# BSK1.net
KiCad netlist of a schematic drawn in EAGLE
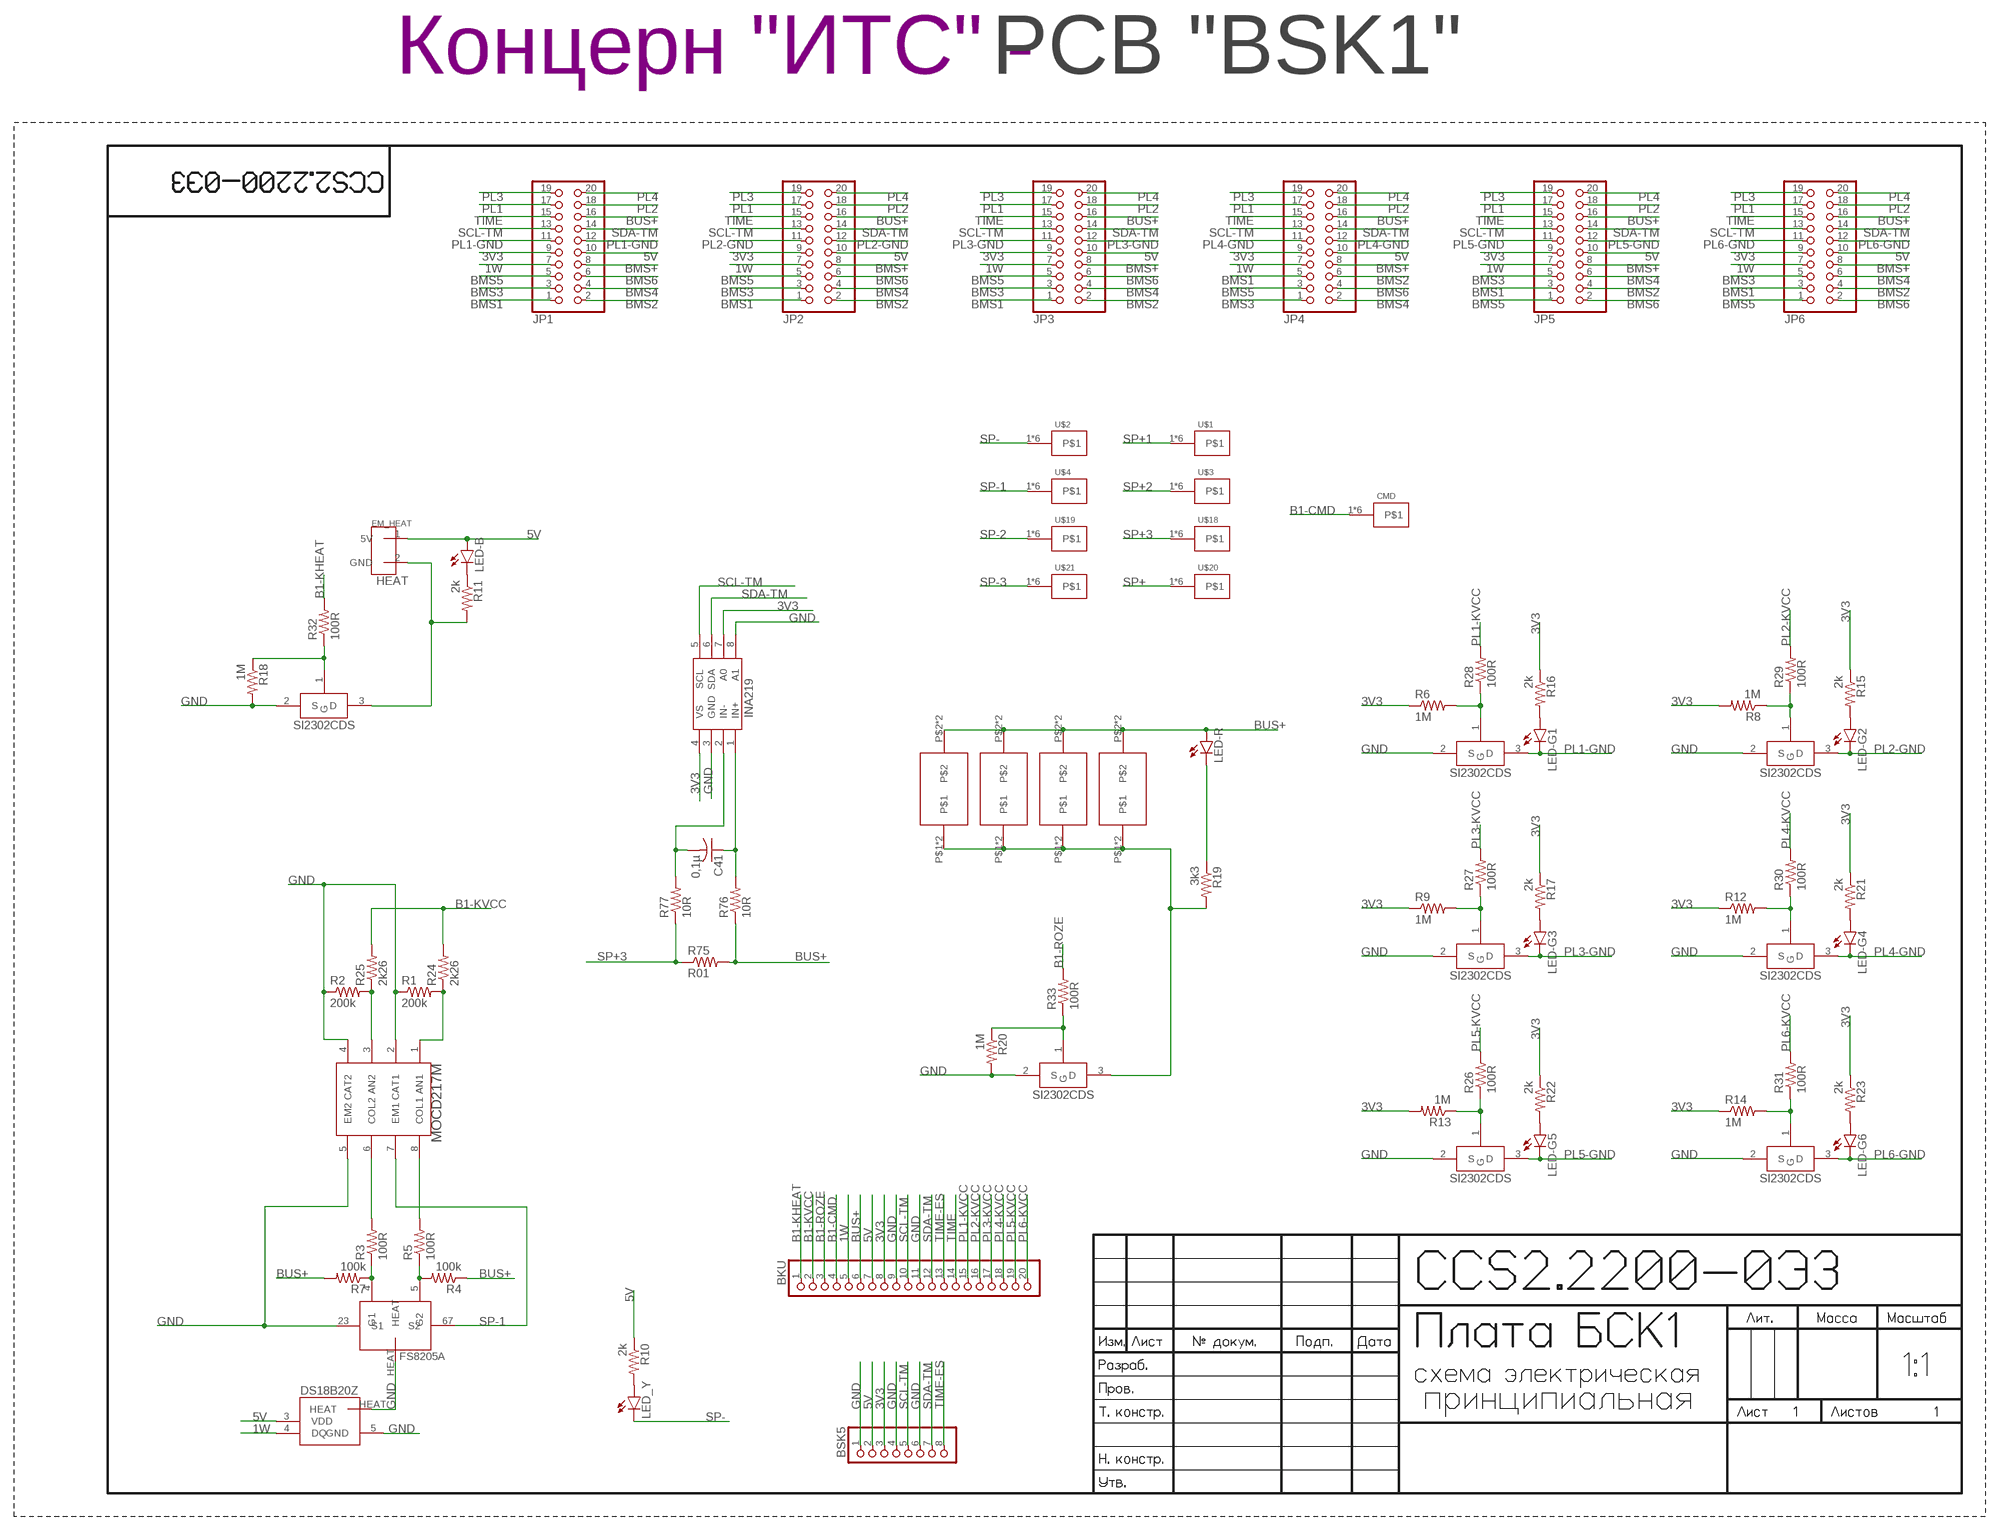
[diagram p0: schematic, sheet 1]

(export (version "E")
  (design (tool "Eeschema 10.0.6"))
  (components
    (comp (ref "BKU")
      (value "PINHD-1X20")
      (footprint "eagle-import:1X20")
      (libsource (lib "eagle-import") (part "PINHD-1X20"))
    )
    (comp (ref "BSK5")
      (value "PINHD-1X8")
      (footprint "eagle-import:1X08")
      (libsource (lib "eagle-import") (part "PINHD-1X8"))
    )
    (comp (ref "C41")
      (value "0,1µ")
      (footprint "eagle-import:C0603")
      (libsource (lib "eagle-import") (part "C-USC0603"))
    )
    (comp (ref "CMD")
      (value "KCONNECTQUAD")
      (footprint "eagle-import:KCONNECT_QUAD")
      (libsource (lib "eagle-import") (part "KCONNECTQUAD"))
    )
    (comp (ref "DS18B20Z")
      (value "DS18B20Z")
      (footprint "eagle-import:SOIC8+HEAT_S")
      (libsource (lib "eagle-import") (part "DS18B20Z"))
    )
    (comp (ref "FS8205")
      (value "FS8205A+")
      (footprint "eagle-import:FS8205A+")
      (libsource (lib "eagle-import") (part "FS8205A+"))
    )
    (comp (ref "INA")
      (value "INA219AID")
      (footprint "eagle-import:SOT23-8")
      (libsource (lib "eagle-import") (part "INA219AID"))
    )
    (comp (ref "JP1")
      (value "PINHD-2X10")
      (footprint "eagle-import:2X10")
      (libsource (lib "eagle-import") (part "PINHD-2X10"))
    )
    (comp (ref "JP2")
      (value "PINHD-2X10")
      (footprint "eagle-import:2X10")
      (libsource (lib "eagle-import") (part "PINHD-2X10"))
    )
    (comp (ref "JP3")
      (value "PINHD-2X10")
      (footprint "eagle-import:2X10")
      (libsource (lib "eagle-import") (part "PINHD-2X10"))
    )
    (comp (ref "JP4")
      (value "PINHD-2X10")
      (footprint "eagle-import:2X10")
      (libsource (lib "eagle-import") (part "PINHD-2X10"))
    )
    (comp (ref "JP5")
      (value "PINHD-2X10")
      (footprint "eagle-import:2X10")
      (libsource (lib "eagle-import") (part "PINHD-2X10"))
    )
    (comp (ref "JP6")
      (value "PINHD-2X10")
      (footprint "eagle-import:2X10")
      (libsource (lib "eagle-import") (part "PINHD-2X10"))
    )
    (comp (ref "LED-B")
      (value "LEDCHIPLED_0603")
      (footprint "eagle-import:CHIPLED_0603")
      (libsource (lib "eagle-import") (part "LEDCHIPLED_0603"))
    )
    (comp (ref "LED-G1")
      (value "LEDCHIPLED_0603")
      (footprint "eagle-import:CHIPLED_0603")
      (libsource (lib "eagle-import") (part "LEDCHIPLED_0603"))
    )
    (comp (ref "LED-G2")
      (value "LEDCHIPLED_0603")
      (footprint "eagle-import:CHIPLED_0603")
      (libsource (lib "eagle-import") (part "LEDCHIPLED_0603"))
    )
    (comp (ref "LED-G3")
      (value "LEDCHIPLED_0603")
      (footprint "eagle-import:CHIPLED_0603")
      (libsource (lib "eagle-import") (part "LEDCHIPLED_0603"))
    )
    (comp (ref "LED-G4")
      (value "LEDCHIPLED_0603")
      (footprint "eagle-import:CHIPLED_0603")
      (libsource (lib "eagle-import") (part "LEDCHIPLED_0603"))
    )
    (comp (ref "LED-G5")
      (value "LEDCHIPLED_0603")
      (footprint "eagle-import:CHIPLED_0603")
      (libsource (lib "eagle-import") (part "LEDCHIPLED_0603"))
    )
    (comp (ref "LED-G6")
      (value "LEDCHIPLED_0603")
      (footprint "eagle-import:CHIPLED_0603")
      (libsource (lib "eagle-import") (part "LEDCHIPLED_0603"))
    )
    (comp (ref "LED-R")
      (value "LEDCHIPLED_0603")
      (footprint "eagle-import:CHIPLED_0603")
      (libsource (lib "eagle-import") (part "LEDCHIPLED_0603"))
    )
    (comp (ref "LED_Y")
      (value "LAP4-BOTTOM")
      (footprint "eagle-import:P47F-BOTTOM")
      (libsource (lib "eagle-import") (part "P4-BOTTOMLA"))
    )
    (comp (ref "R1")
      (value "200k")
      (footprint "eagle-import:R0603")
      (libsource (lib "eagle-import") (part "resistor_R-US_R0603"))
    )
    (comp (ref "R2")
      (value "200k")
      (footprint "eagle-import:R0603")
      (libsource (lib "eagle-import") (part "resistor_R-US_R0603"))
    )
    (comp (ref "R3")
      (value "100R")
      (footprint "eagle-import:R0603")
      (libsource (lib "eagle-import") (part "resistor_R-US_R0603"))
    )
    (comp (ref "R4")
      (value "100k")
      (footprint "eagle-import:R0603")
      (libsource (lib "eagle-import") (part "resistor_R-US_R0603"))
    )
    (comp (ref "R5")
      (value "100R")
      (footprint "eagle-import:R0603")
      (libsource (lib "eagle-import") (part "resistor_R-US_R0603"))
    )
    (comp (ref "R6")
      (value "1M")
      (footprint "eagle-import:R0603")
      (libsource (lib "eagle-import") (part "resistor_R-US_R0603"))
    )
    (comp (ref "R7")
      (value "100k")
      (footprint "eagle-import:R0603")
      (libsource (lib "eagle-import") (part "resistor_R-US_R0603"))
    )
    (comp (ref "R8")
      (value "1M")
      (footprint "eagle-import:R0603")
      (libsource (lib "eagle-import") (part "resistor_R-US_R0603"))
    )
    (comp (ref "R9")
      (value "1M")
      (footprint "eagle-import:R0603")
      (libsource (lib "eagle-import") (part "resistor_R-US_R0603"))
    )
    (comp (ref "R10")
      (value "2k")
      (footprint "eagle-import:R0603")
      (libsource (lib "eagle-import") (part "resistor_R-US_R0603"))
    )
    (comp (ref "R11")
      (value "2k")
      (footprint "eagle-import:R0603")
      (libsource (lib "eagle-import") (part "resistor_R-US_R0603"))
    )
    (comp (ref "R12")
      (value "1M")
      (footprint "eagle-import:R0603")
      (libsource (lib "eagle-import") (part "resistor_R-US_R0603"))
    )
    (comp (ref "R13")
      (value "1M")
      (footprint "eagle-import:R0603")
      (libsource (lib "eagle-import") (part "resistor_R-US_R0603"))
    )
    (comp (ref "R14")
      (value "1M")
      (footprint "eagle-import:R0603")
      (libsource (lib "eagle-import") (part "resistor_R-US_R0603"))
    )
    (comp (ref "R15")
      (value "2k")
      (footprint "eagle-import:R0603")
      (libsource (lib "eagle-import") (part "resistor_R-US_R0603"))
    )
    (comp (ref "R16")
      (value "2k")
      (footprint "eagle-import:R0603")
      (libsource (lib "eagle-import") (part "resistor_R-US_R0603"))
    )
    (comp (ref "R17")
      (value "2k")
      (footprint "eagle-import:R0603")
      (libsource (lib "eagle-import") (part "resistor_R-US_R0603"))
    )
    (comp (ref "R18")
      (value "1M")
      (footprint "eagle-import:R0603")
      (libsource (lib "eagle-import") (part "resistor_R-US_R0603"))
    )
    (comp (ref "R19")
      (value "3k3")
      (footprint "eagle-import:R0603")
      (libsource (lib "eagle-import") (part "resistor_R-US_R0603"))
    )
    (comp (ref "R20")
      (value "1M")
      (footprint "eagle-import:R0603")
      (libsource (lib "eagle-import") (part "resistor_R-US_R0603"))
    )
    (comp (ref "R21")
      (value "2k")
      (footprint "eagle-import:R0603")
      (libsource (lib "eagle-import") (part "resistor_R-US_R0603"))
    )
    (comp (ref "R22")
      (value "2k")
      (footprint "eagle-import:R0603")
      (libsource (lib "eagle-import") (part "resistor_R-US_R0603"))
    )
    (comp (ref "R23")
      (value "2k")
      (footprint "eagle-import:R0603")
      (libsource (lib "eagle-import") (part "resistor_R-US_R0603"))
    )
    (comp (ref "R24")
      (value "2k26")
      (footprint "eagle-import:R0603")
      (libsource (lib "eagle-import") (part "resistor_R-US_R0603"))
    )
    (comp (ref "R25")
      (value "2k26")
      (footprint "eagle-import:R0603")
      (libsource (lib "eagle-import") (part "resistor_R-US_R0603"))
    )
    (comp (ref "R26")
      (value "100R")
      (footprint "eagle-import:R0603")
      (libsource (lib "eagle-import") (part "resistor_R-US_R0603"))
    )
    (comp (ref "R27")
      (value "100R")
      (footprint "eagle-import:R0603")
      (libsource (lib "eagle-import") (part "resistor_R-US_R0603"))
    )
    (comp (ref "R28")
      (value "100R")
      (footprint "eagle-import:R0603")
      (libsource (lib "eagle-import") (part "resistor_R-US_R0603"))
    )
    (comp (ref "R29")
      (value "100R")
      (footprint "eagle-import:R0603")
      (libsource (lib "eagle-import") (part "resistor_R-US_R0603"))
    )
    (comp (ref "R30")
      (value "100R")
      (footprint "eagle-import:R0603")
      (libsource (lib "eagle-import") (part "resistor_R-US_R0603"))
    )
    (comp (ref "R31")
      (value "100R")
      (footprint "eagle-import:R0603")
      (libsource (lib "eagle-import") (part "resistor_R-US_R0603"))
    )
    (comp (ref "R32")
      (value "100R")
      (footprint "eagle-import:R0603")
      (libsource (lib "eagle-import") (part "resistor_R-US_R0603"))
    )
    (comp (ref "R33")
      (value "100R")
      (footprint "eagle-import:R0603")
      (libsource (lib "eagle-import") (part "resistor_R-US_R0603"))
    )
    (comp (ref "R75")
      (value "R01")
      (footprint "eagle-import:R2512")
      (libsource (lib "eagle-import") (part "R-US_R2512"))
    )
    (comp (ref "R76")
      (value "10R")
      (footprint "eagle-import:R0603")
      (libsource (lib "eagle-import") (part "resistor_R-US_R0603"))
    )
    (comp (ref "R77")
      (value "10R")
      (footprint "eagle-import:R0603")
      (libsource (lib "eagle-import") (part "resistor_R-US_R0603"))
    )
    (comp (ref "SI2302-1")
      (value "SI2302CDS")
      (footprint "eagle-import:SOT23-3")
      (libsource (lib "eagle-import") (part "SI2302CDS"))
    )
    (comp (ref "SI2302-2")
      (value "SI2302CDS")
      (footprint "eagle-import:SOT23-3")
      (libsource (lib "eagle-import") (part "SI2302CDS"))
    )
    (comp (ref "SI2302-3")
      (value "SI2302CDS")
      (footprint "eagle-import:SOT23-3")
      (libsource (lib "eagle-import") (part "SI2302CDS"))
    )
    (comp (ref "SI2302-4")
      (value "SI2302CDS")
      (footprint "eagle-import:SOT23-3")
      (libsource (lib "eagle-import") (part "SI2302CDS"))
    )
    (comp (ref "SI2302-5")
      (value "SI2302CDS")
      (footprint "eagle-import:SOT23-3")
      (libsource (lib "eagle-import") (part "SI2302CDS"))
    )
    (comp (ref "SI2302-6")
      (value "SI2302CDS")
      (footprint "eagle-import:SOT23-3")
      (libsource (lib "eagle-import") (part "SI2302CDS"))
    )
    (comp (ref "SI2302-7")
      (value "SI2302CDS")
      (footprint "eagle-import:SOT23-3")
      (libsource (lib "eagle-import") (part "SI2302CDS"))
    )
    (comp (ref "SI2302-8")
      (value "SI2302CDS")
      (footprint "eagle-import:SOT23-3")
      (libsource (lib "eagle-import") (part "SI2302CDS"))
    )
    (comp (ref "U$1")
      (value "KCONNECT")
      (footprint "eagle-import:KCONNECT")
      (libsource (lib "eagle-import") (part "KCONNECT"))
    )
    (comp (ref "U$2")
      (value "KCONNECT")
      (footprint "eagle-import:KCONNECT")
      (libsource (lib "eagle-import") (part "KCONNECT"))
    )
    (comp (ref "U$3")
      (value "KCONNECT")
      (footprint "eagle-import:KCONNECT")
      (libsource (lib "eagle-import") (part "KCONNECT"))
    )
    (comp (ref "U$4")
      (value "KCONNECT")
      (footprint "eagle-import:KCONNECT")
      (libsource (lib "eagle-import") (part "KCONNECT"))
    )
    (comp (ref "U$18")
      (value "KCONNECT")
      (footprint "eagle-import:KCONNECT")
      (libsource (lib "eagle-import") (part "KCONNECT"))
    )
    (comp (ref "U$19")
      (value "KCONNECT")
      (footprint "eagle-import:KCONNECT")
      (libsource (lib "eagle-import") (part "KCONNECT"))
    )
    (comp (ref "U$20")
      (value "KCONNECT")
      (footprint "eagle-import:KCONNECT")
      (libsource (lib "eagle-import") (part "KCONNECT"))
    )
    (comp (ref "U$21")
      (value "KCONNECT")
      (footprint "eagle-import:KCONNECT")
      (libsource (lib "eagle-import") (part "KCONNECT"))
    )
    (comp (ref "U$22")
      (value "MOCD")
      (footprint "eagle-import:SOIC8")
      (libsource (lib "eagle-import") (part "MOCD217M"))
    )
    (comp (ref "U$24")
      (value "EM_HEAT")
      (footprint "eagle-import:EM_HEAT")
      (libsource (lib "eagle-import") (part "EM_HEAT"))
    )
    (comp (ref "U$26")
      (value "PCB \"BSK1\"")
      (footprint "eagle-import:ITS-LOGO")
      (libsource (lib "eagle-import") (part "ITS-LOGOPCB-{dblquote}{dblquote}"))
    )
    (comp (ref "U$27")
      (value "GRAFITGRAFIT4_2")
      (footprint "eagle-import:GRAFIT4_2")
      (libsource (lib "eagle-import") (part "GRAFITGRAFIT4_2"))
    )
    (comp (ref "U$28")
      (value "GRAFITGRAFIT4_2")
      (footprint "eagle-import:GRAFIT4_2")
      (libsource (lib "eagle-import") (part "GRAFITGRAFIT4_2"))
    )
    (comp (ref "U$29")
      (value "GRAFITGRAFIT4_2")
      (footprint "eagle-import:GRAFIT4_2")
      (libsource (lib "eagle-import") (part "GRAFITGRAFIT4_2"))
    )
    (comp (ref "U$30")
      (value "GRAFITGRAFIT4_2")
      (footprint "eagle-import:GRAFIT4_2")
      (libsource (lib "eagle-import") (part "GRAFITGRAFIT4_2"))
    )
  )
  (nets
    (net (code "1") (name "/1W") (class "Default")
      (node (ref "BKU") (pin "5") (pinfunction "5_5") (pintype "passive"))
      (node (ref "DS18B20Z") (pin "4") (pinfunction "DQ_4") (pintype "bidirectional"))
      (node (ref "JP1") (pin "7") (pinfunction "7_7") (pintype "passive"))
      (node (ref "JP2") (pin "7") (pinfunction "7_7") (pintype "passive"))
      (node (ref "JP3") (pin "7") (pinfunction "7_7") (pintype "passive"))
      (node (ref "JP4") (pin "7") (pinfunction "7_7") (pintype "passive"))
      (node (ref "JP5") (pin "7") (pinfunction "7_7") (pintype "passive"))
      (node (ref "JP6") (pin "7") (pinfunction "7_7") (pintype "passive"))
    )
    (net (code "2") (name "/3V3") (class "Default")
      (node (ref "BKU") (pin "8") (pinfunction "8_8") (pintype "passive"))
      (node (ref "BSK5") (pin "3") (pinfunction "3_3") (pintype "passive"))
      (node (ref "INA") (pin "4") (pinfunction "VS_4") (pintype "bidirectional"))
      (node (ref "INA") (pin "7") (pinfunction "A0_7") (pintype "bidirectional"))
      (node (ref "JP1") (pin "9") (pinfunction "9_9") (pintype "passive"))
      (node (ref "JP2") (pin "9") (pinfunction "9_9") (pintype "passive"))
      (node (ref "JP3") (pin "9") (pinfunction "9_9") (pintype "passive"))
      (node (ref "JP4") (pin "9") (pinfunction "9_9") (pintype "passive"))
      (node (ref "JP5") (pin "9") (pinfunction "9_9") (pintype "passive"))
      (node (ref "JP6") (pin "9") (pinfunction "9_9") (pintype "passive"))
      (node (ref "R12") (pin "1") (pinfunction "1_1") (pintype "passive"))
      (node (ref "R13") (pin "2") (pinfunction "2_2") (pintype "passive"))
      (node (ref "R14") (pin "1") (pinfunction "1_1") (pintype "passive"))
      (node (ref "R15") (pin "1") (pinfunction "1_1") (pintype "passive"))
      (node (ref "R16") (pin "1") (pinfunction "1_1") (pintype "passive"))
      (node (ref "R17") (pin "1") (pinfunction "1_1") (pintype "passive"))
      (node (ref "R21") (pin "1") (pinfunction "1_1") (pintype "passive"))
      (node (ref "R22") (pin "1") (pinfunction "1_1") (pintype "passive"))
      (node (ref "R23") (pin "1") (pinfunction "1_1") (pintype "passive"))
      (node (ref "R6") (pin "1") (pinfunction "1_1") (pintype "passive"))
      (node (ref "R8") (pin "2") (pinfunction "2_2") (pintype "passive"))
      (node (ref "R9") (pin "1") (pinfunction "1_1") (pintype "passive"))
    )
    (net (code "3") (name "/5V") (class "Default")
      (node (ref "BKU") (pin "7") (pinfunction "7_7") (pintype "passive"))
      (node (ref "BSK5") (pin "2") (pinfunction "2_2") (pintype "passive"))
      (node (ref "DS18B20Z") (pin "3") (pinfunction "VDD_3") (pintype "bidirectional"))
      (node (ref "JP1") (pin "10") (pinfunction "10_10") (pintype "passive"))
      (node (ref "JP2") (pin "10") (pinfunction "10_10") (pintype "passive"))
      (node (ref "JP3") (pin "10") (pinfunction "10_10") (pintype "passive"))
      (node (ref "JP4") (pin "10") (pinfunction "10_10") (pintype "passive"))
      (node (ref "JP5") (pin "10") (pinfunction "10_10") (pintype "passive"))
      (node (ref "JP6") (pin "10") (pinfunction "10_10") (pintype "passive"))
      (node (ref "LED-B") (pin "A") (pinfunction "A_A") (pintype "passive"))
      (node (ref "R10") (pin "1") (pinfunction "1_1") (pintype "passive"))
      (node (ref "U$24") (pin "1") (pinfunction "5V_1") (pintype "bidirectional"))
    )
    (net (code "4") (name "/B1-CMD") (class "Default")
      (node (ref "BKU") (pin "4") (pinfunction "4_4") (pintype "passive"))
      (node (ref "CMD") (pin "1") (pinfunction "P$1_1") (pintype "bidirectional"))
      (node (ref "CMD") (pin "2") (pinfunction "P$1_2") (pintype "bidirectional"))
      (node (ref "CMD") (pin "3") (pinfunction "P$1_3") (pintype "bidirectional"))
      (node (ref "CMD") (pin "4") (pinfunction "P$1_4") (pintype "bidirectional"))
      (node (ref "CMD") (pin "P$1") (pinfunction "P$1_P$1") (pintype "bidirectional"))
      (node (ref "CMD") (pin "P$2") (pinfunction "P$1_P$2") (pintype "bidirectional"))
    )
    (net (code "5") (name "/B1-KHEAT") (class "Default")
      (node (ref "BKU") (pin "1") (pinfunction "1_1") (pintype "passive"))
      (node (ref "R32") (pin "2") (pinfunction "2_2") (pintype "passive"))
    )
    (net (code "6") (name "/B1-KVCC") (class "Default")
      (node (ref "BKU") (pin "2") (pinfunction "2_2") (pintype "passive"))
      (node (ref "R24") (pin "2") (pinfunction "2_2") (pintype "passive"))
      (node (ref "R25") (pin "2") (pinfunction "2_2") (pintype "passive"))
    )
    (net (code "7") (name "/B1-ROZE") (class "Default")
      (node (ref "BKU") (pin "3") (pinfunction "3_3") (pintype "passive"))
      (node (ref "R33") (pin "2") (pinfunction "2_2") (pintype "passive"))
    )
    (net (code "8") (name "/BMS+") (class "Default")
      (node (ref "JP1") (pin "8") (pinfunction "8_8") (pintype "passive"))
      (node (ref "JP2") (pin "8") (pinfunction "8_8") (pintype "passive"))
      (node (ref "JP3") (pin "8") (pinfunction "8_8") (pintype "passive"))
      (node (ref "JP4") (pin "8") (pinfunction "8_8") (pintype "passive"))
      (node (ref "JP5") (pin "8") (pinfunction "8_8") (pintype "passive"))
      (node (ref "JP6") (pin "8") (pinfunction "8_8") (pintype "passive"))
    )
    (net (code "9") (name "/BMS1") (class "Default")
      (node (ref "JP1") (pin "1") (pinfunction "1_1") (pintype "passive"))
      (node (ref "JP2") (pin "1") (pinfunction "1_1") (pintype "passive"))
      (node (ref "JP3") (pin "1") (pinfunction "1_1") (pintype "passive"))
      (node (ref "JP4") (pin "5") (pinfunction "5_5") (pintype "passive"))
      (node (ref "JP5") (pin "3") (pinfunction "3_3") (pintype "passive"))
      (node (ref "JP6") (pin "3") (pinfunction "3_3") (pintype "passive"))
    )
    (net (code "10") (name "/BMS2") (class "Default")
      (node (ref "JP1") (pin "2") (pinfunction "2_2") (pintype "passive"))
      (node (ref "JP2") (pin "2") (pinfunction "2_2") (pintype "passive"))
      (node (ref "JP3") (pin "2") (pinfunction "2_2") (pintype "passive"))
      (node (ref "JP4") (pin "6") (pinfunction "6_6") (pintype "passive"))
      (node (ref "JP5") (pin "4") (pinfunction "4_4") (pintype "passive"))
      (node (ref "JP6") (pin "4") (pinfunction "4_4") (pintype "passive"))
    )
    (net (code "11") (name "/BMS3") (class "Default")
      (node (ref "JP1") (pin "3") (pinfunction "3_3") (pintype "passive"))
      (node (ref "JP2") (pin "3") (pinfunction "3_3") (pintype "passive"))
      (node (ref "JP3") (pin "3") (pinfunction "3_3") (pintype "passive"))
      (node (ref "JP4") (pin "1") (pinfunction "1_1") (pintype "passive"))
      (node (ref "JP5") (pin "5") (pinfunction "5_5") (pintype "passive"))
      (node (ref "JP6") (pin "5") (pinfunction "5_5") (pintype "passive"))
    )
    (net (code "12") (name "/BMS4") (class "Default")
      (node (ref "JP1") (pin "4") (pinfunction "4_4") (pintype "passive"))
      (node (ref "JP2") (pin "4") (pinfunction "4_4") (pintype "passive"))
      (node (ref "JP3") (pin "4") (pinfunction "4_4") (pintype "passive"))
      (node (ref "JP4") (pin "2") (pinfunction "2_2") (pintype "passive"))
      (node (ref "JP5") (pin "6") (pinfunction "6_6") (pintype "passive"))
      (node (ref "JP6") (pin "6") (pinfunction "6_6") (pintype "passive"))
    )
    (net (code "13") (name "/BMS5") (class "Default")
      (node (ref "JP1") (pin "5") (pinfunction "5_5") (pintype "passive"))
      (node (ref "JP2") (pin "5") (pinfunction "5_5") (pintype "passive"))
      (node (ref "JP3") (pin "5") (pinfunction "5_5") (pintype "passive"))
      (node (ref "JP4") (pin "3") (pinfunction "3_3") (pintype "passive"))
      (node (ref "JP5") (pin "1") (pinfunction "1_1") (pintype "passive"))
      (node (ref "JP6") (pin "1") (pinfunction "1_1") (pintype "passive"))
    )
    (net (code "14") (name "/BMS6") (class "Default")
      (node (ref "JP1") (pin "6") (pinfunction "6_6") (pintype "passive"))
      (node (ref "JP2") (pin "6") (pinfunction "6_6") (pintype "passive"))
      (node (ref "JP3") (pin "6") (pinfunction "6_6") (pintype "passive"))
      (node (ref "JP4") (pin "4") (pinfunction "4_4") (pintype "passive"))
      (node (ref "JP5") (pin "2") (pinfunction "2_2") (pintype "passive"))
      (node (ref "JP6") (pin "2") (pinfunction "2_2") (pintype "passive"))
    )
    (net (code "15") (name "/BUS+") (class "Default")
      (node (ref "BKU") (pin "6") (pinfunction "6_6") (pintype "passive"))
      (node (ref "JP1") (pin "16") (pinfunction "16_16") (pintype "passive"))
      (node (ref "JP2") (pin "16") (pinfunction "16_16") (pintype "passive"))
      (node (ref "JP3") (pin "16") (pinfunction "16_16") (pintype "passive"))
      (node (ref "JP4") (pin "16") (pinfunction "16_16") (pintype "passive"))
      (node (ref "JP5") (pin "16") (pinfunction "16_16") (pintype "passive"))
      (node (ref "JP6") (pin "16") (pinfunction "16_16") (pintype "passive"))
      (node (ref "LED-R") (pin "A") (pinfunction "A_A") (pintype "passive"))
      (node (ref "R4") (pin "1") (pinfunction "1_1") (pintype "passive"))
      (node (ref "R7") (pin "2") (pinfunction "2_2") (pintype "passive"))
      (node (ref "R75") (pin "2") (pinfunction "2_2") (pintype "passive"))
      (node (ref "R76") (pin "1") (pinfunction "1_1") (pintype "passive"))
      (node (ref "U$27") (pin "P$2") (pinfunction "P$2_P$2") (pintype "bidirectional"))
      (node (ref "U$27") (pin "P$5") (pinfunction "P$2_P$5") (pintype "bidirectional"))
      (node (ref "U$28") (pin "P$2") (pinfunction "P$2_P$2") (pintype "bidirectional"))
      (node (ref "U$28") (pin "P$5") (pinfunction "P$2_P$5") (pintype "bidirectional"))
      (node (ref "U$29") (pin "P$2") (pinfunction "P$2_P$2") (pintype "bidirectional"))
      (node (ref "U$29") (pin "P$5") (pinfunction "P$2_P$5") (pintype "bidirectional"))
      (node (ref "U$30") (pin "P$2") (pinfunction "P$2_P$2") (pintype "bidirectional"))
      (node (ref "U$30") (pin "P$5") (pinfunction "P$2_P$5") (pintype "bidirectional"))
    )
    (net (code "16") (name "/GND") (class "Default")
      (node (ref "BKU") (pin "11") (pinfunction "11_11") (pintype "passive"))
      (node (ref "BKU") (pin "9") (pinfunction "9_9") (pintype "passive"))
      (node (ref "BSK5") (pin "1") (pinfunction "1_1") (pintype "passive"))
      (node (ref "BSK5") (pin "4") (pinfunction "4_4") (pintype "passive"))
      (node (ref "BSK5") (pin "6") (pinfunction "6_6") (pintype "passive"))
      (node (ref "DS18B20Z") (pin "5") (pinfunction "GND_5") (pintype "bidirectional"))
      (node (ref "DS18B20Z") (pin "HEAT") (pinfunction "HEAT_HEAT") (pintype "bidirectional"))
      (node (ref "FS8205") (pin "23") (pinfunction "S1_23") (pintype "bidirectional"))
      (node (ref "FS8205") (pin "HEAT") (pinfunction "HEAT_HEAT") (pintype "bidirectional"))
      (node (ref "INA") (pin "3") (pinfunction "GND_3") (pintype "bidirectional"))
      (node (ref "INA") (pin "8") (pinfunction "A1_8") (pintype "bidirectional"))
      (node (ref "R1") (pin "1") (pinfunction "1_1") (pintype "passive"))
      (node (ref "R18") (pin "2") (pinfunction "2_2") (pintype "passive"))
      (node (ref "R2") (pin "1") (pinfunction "1_1") (pintype "passive"))
      (node (ref "R20") (pin "2") (pinfunction "2_2") (pintype "passive"))
      (node (ref "SI2302-1") (pin "2") (pinfunction "S_2") (pintype "bidirectional"))
      (node (ref "SI2302-2") (pin "2") (pinfunction "S_2") (pintype "bidirectional"))
      (node (ref "SI2302-3") (pin "2") (pinfunction "S_2") (pintype "bidirectional"))
      (node (ref "SI2302-4") (pin "2") (pinfunction "S_2") (pintype "bidirectional"))
      (node (ref "SI2302-5") (pin "2") (pinfunction "S_2") (pintype "bidirectional"))
      (node (ref "SI2302-6") (pin "2") (pinfunction "S_2") (pintype "bidirectional"))
      (node (ref "SI2302-7") (pin "2") (pinfunction "S_2") (pintype "bidirectional"))
      (node (ref "SI2302-8") (pin "2") (pinfunction "S_2") (pintype "bidirectional"))
      (node (ref "U$22") (pin "2") (pinfunction "CAT1_2") (pintype "bidirectional"))
      (node (ref "U$22") (pin "4") (pinfunction "CAT2_4") (pintype "bidirectional"))
      (node (ref "U$22") (pin "5") (pinfunction "EM2_5") (pintype "bidirectional"))
    )
    (net (code "17") (name "/PL1") (class "Default")
      (node (ref "JP1") (pin "17") (pinfunction "17_17") (pintype "passive"))
      (node (ref "JP2") (pin "17") (pinfunction "17_17") (pintype "passive"))
      (node (ref "JP3") (pin "17") (pinfunction "17_17") (pintype "passive"))
      (node (ref "JP4") (pin "17") (pinfunction "17_17") (pintype "passive"))
      (node (ref "JP5") (pin "17") (pinfunction "17_17") (pintype "passive"))
      (node (ref "JP6") (pin "17") (pinfunction "17_17") (pintype "passive"))
    )
    (net (code "18") (name "/PL1-GND") (class "Default")
      (node (ref "JP1") (pin "11") (pinfunction "11_11") (pintype "passive"))
      (node (ref "JP1") (pin "12") (pinfunction "12_12") (pintype "passive"))
      (node (ref "LED-G1") (pin "C") (pinfunction "C_C") (pintype "passive"))
      (node (ref "SI2302-8") (pin "3") (pinfunction "D_3") (pintype "bidirectional"))
    )
    (net (code "19") (name "/PL1-KVCC") (class "Default")
      (node (ref "BKU") (pin "15") (pinfunction "15_15") (pintype "passive"))
      (node (ref "R28") (pin "2") (pinfunction "2_2") (pintype "passive"))
    )
    (net (code "20") (name "/PL2") (class "Default")
      (node (ref "JP1") (pin "18") (pinfunction "18_18") (pintype "passive"))
      (node (ref "JP2") (pin "18") (pinfunction "18_18") (pintype "passive"))
      (node (ref "JP3") (pin "18") (pinfunction "18_18") (pintype "passive"))
      (node (ref "JP4") (pin "18") (pinfunction "18_18") (pintype "passive"))
      (node (ref "JP5") (pin "18") (pinfunction "18_18") (pintype "passive"))
      (node (ref "JP6") (pin "18") (pinfunction "18_18") (pintype "passive"))
    )
    (net (code "21") (name "/PL2-GND") (class "Default")
      (node (ref "JP2") (pin "11") (pinfunction "11_11") (pintype "passive"))
      (node (ref "JP2") (pin "12") (pinfunction "12_12") (pintype "passive"))
      (node (ref "LED-G2") (pin "C") (pinfunction "C_C") (pintype "passive"))
      (node (ref "SI2302-7") (pin "3") (pinfunction "D_3") (pintype "bidirectional"))
    )
    (net (code "22") (name "/PL2-KVCC") (class "Default")
      (node (ref "BKU") (pin "16") (pinfunction "16_16") (pintype "passive"))
      (node (ref "R29") (pin "2") (pinfunction "2_2") (pintype "passive"))
    )
    (net (code "23") (name "/PL3") (class "Default")
      (node (ref "JP1") (pin "19") (pinfunction "19_19") (pintype "passive"))
      (node (ref "JP2") (pin "19") (pinfunction "19_19") (pintype "passive"))
      (node (ref "JP3") (pin "19") (pinfunction "19_19") (pintype "passive"))
      (node (ref "JP4") (pin "19") (pinfunction "19_19") (pintype "passive"))
      (node (ref "JP5") (pin "19") (pinfunction "19_19") (pintype "passive"))
      (node (ref "JP6") (pin "19") (pinfunction "19_19") (pintype "passive"))
    )
    (net (code "24") (name "/PL3-GND") (class "Default")
      (node (ref "JP3") (pin "11") (pinfunction "11_11") (pintype "passive"))
      (node (ref "JP3") (pin "12") (pinfunction "12_12") (pintype "passive"))
      (node (ref "LED-G3") (pin "C") (pinfunction "C_C") (pintype "passive"))
      (node (ref "SI2302-6") (pin "3") (pinfunction "D_3") (pintype "bidirectional"))
    )
    (net (code "25") (name "/PL3-KVCC") (class "Default")
      (node (ref "BKU") (pin "17") (pinfunction "17_17") (pintype "passive"))
      (node (ref "R27") (pin "2") (pinfunction "2_2") (pintype "passive"))
    )
    (net (code "26") (name "/PL4") (class "Default")
      (node (ref "JP1") (pin "20") (pinfunction "20_20") (pintype "passive"))
      (node (ref "JP2") (pin "20") (pinfunction "20_20") (pintype "passive"))
      (node (ref "JP3") (pin "20") (pinfunction "20_20") (pintype "passive"))
      (node (ref "JP4") (pin "20") (pinfunction "20_20") (pintype "passive"))
      (node (ref "JP5") (pin "20") (pinfunction "20_20") (pintype "passive"))
      (node (ref "JP6") (pin "20") (pinfunction "20_20") (pintype "passive"))
    )
    (net (code "27") (name "/PL4-GND") (class "Default")
      (node (ref "JP4") (pin "11") (pinfunction "11_11") (pintype "passive"))
      (node (ref "JP4") (pin "12") (pinfunction "12_12") (pintype "passive"))
      (node (ref "LED-G4") (pin "C") (pinfunction "C_C") (pintype "passive"))
      (node (ref "SI2302-5") (pin "3") (pinfunction "D_3") (pintype "bidirectional"))
    )
    (net (code "28") (name "/PL4-KVCC") (class "Default")
      (node (ref "BKU") (pin "18") (pinfunction "18_18") (pintype "passive"))
      (node (ref "R30") (pin "2") (pinfunction "2_2") (pintype "passive"))
    )
    (net (code "29") (name "/PL5-GND") (class "Default")
      (node (ref "JP5") (pin "11") (pinfunction "11_11") (pintype "passive"))
      (node (ref "JP5") (pin "12") (pinfunction "12_12") (pintype "passive"))
      (node (ref "LED-G5") (pin "C") (pinfunction "C_C") (pintype "passive"))
      (node (ref "SI2302-4") (pin "3") (pinfunction "D_3") (pintype "bidirectional"))
    )
    (net (code "30") (name "/PL5-KVCC") (class "Default")
      (node (ref "BKU") (pin "19") (pinfunction "19_19") (pintype "passive"))
      (node (ref "R26") (pin "2") (pinfunction "2_2") (pintype "passive"))
    )
    (net (code "31") (name "/PL6-GND") (class "Default")
      (node (ref "JP6") (pin "11") (pinfunction "11_11") (pintype "passive"))
      (node (ref "JP6") (pin "12") (pinfunction "12_12") (pintype "passive"))
      (node (ref "LED-G6") (pin "C") (pinfunction "C_C") (pintype "passive"))
      (node (ref "SI2302-3") (pin "3") (pinfunction "D_3") (pintype "bidirectional"))
    )
    (net (code "32") (name "/PL6-KVCC") (class "Default")
      (node (ref "BKU") (pin "20") (pinfunction "20_20") (pintype "passive"))
      (node (ref "R31") (pin "2") (pinfunction "2_2") (pintype "passive"))
    )
    (net (code "33") (name "/SCL-TM") (class "Default")
      (node (ref "BKU") (pin "10") (pinfunction "10_10") (pintype "passive"))
      (node (ref "BSK5") (pin "5") (pinfunction "5_5") (pintype "passive"))
      (node (ref "INA") (pin "5") (pinfunction "SCL_5") (pintype "bidirectional"))
      (node (ref "JP1") (pin "13") (pinfunction "13_13") (pintype "passive"))
      (node (ref "JP2") (pin "13") (pinfunction "13_13") (pintype "passive"))
      (node (ref "JP3") (pin "13") (pinfunction "13_13") (pintype "passive"))
      (node (ref "JP4") (pin "13") (pinfunction "13_13") (pintype "passive"))
      (node (ref "JP5") (pin "13") (pinfunction "13_13") (pintype "passive"))
      (node (ref "JP6") (pin "13") (pinfunction "13_13") (pintype "passive"))
    )
    (net (code "34") (name "/SDA-TM") (class "Default")
      (node (ref "BKU") (pin "12") (pinfunction "12_12") (pintype "passive"))
      (node (ref "BSK5") (pin "7") (pinfunction "7_7") (pintype "passive"))
      (node (ref "INA") (pin "6") (pinfunction "SDA_6") (pintype "bidirectional"))
      (node (ref "JP1") (pin "14") (pinfunction "14_14") (pintype "passive"))
      (node (ref "JP2") (pin "14") (pinfunction "14_14") (pintype "passive"))
      (node (ref "JP3") (pin "14") (pinfunction "14_14") (pintype "passive"))
      (node (ref "JP4") (pin "14") (pinfunction "14_14") (pintype "passive"))
      (node (ref "JP5") (pin "14") (pinfunction "14_14") (pintype "passive"))
      (node (ref "JP6") (pin "14") (pinfunction "14_14") (pintype "passive"))
    )
    (net (code "35") (name "/SP+") (class "Default")
      (node (ref "U$20") (pin "1") (pinfunction "P$1_1") (pintype "bidirectional"))
      (node (ref "U$20") (pin "2") (pinfunction "P$1_2") (pintype "bidirectional"))
      (node (ref "U$20") (pin "3") (pinfunction "P$1_3") (pintype "bidirectional"))
      (node (ref "U$20") (pin "4") (pinfunction "P$1_4") (pintype "bidirectional"))
      (node (ref "U$20") (pin "P$1") (pinfunction "P$1_P$1") (pintype "bidirectional"))
      (node (ref "U$20") (pin "P$2") (pinfunction "P$1_P$2") (pintype "bidirectional"))
    )
    (net (code "36") (name "/SP+1") (class "Default")
      (node (ref "U$1") (pin "1") (pinfunction "P$1_1") (pintype "bidirectional"))
      (node (ref "U$1") (pin "2") (pinfunction "P$1_2") (pintype "bidirectional"))
      (node (ref "U$1") (pin "3") (pinfunction "P$1_3") (pintype "bidirectional"))
      (node (ref "U$1") (pin "4") (pinfunction "P$1_4") (pintype "bidirectional"))
      (node (ref "U$1") (pin "P$1") (pinfunction "P$1_P$1") (pintype "bidirectional"))
      (node (ref "U$1") (pin "P$2") (pinfunction "P$1_P$2") (pintype "bidirectional"))
    )
    (net (code "37") (name "/SP+2") (class "Default")
      (node (ref "U$3") (pin "1") (pinfunction "P$1_1") (pintype "bidirectional"))
      (node (ref "U$3") (pin "2") (pinfunction "P$1_2") (pintype "bidirectional"))
      (node (ref "U$3") (pin "3") (pinfunction "P$1_3") (pintype "bidirectional"))
      (node (ref "U$3") (pin "4") (pinfunction "P$1_4") (pintype "bidirectional"))
      (node (ref "U$3") (pin "P$1") (pinfunction "P$1_P$1") (pintype "bidirectional"))
      (node (ref "U$3") (pin "P$2") (pinfunction "P$1_P$2") (pintype "bidirectional"))
    )
    (net (code "38") (name "/SP+3") (class "Default")
      (node (ref "R75") (pin "1") (pinfunction "1_1") (pintype "passive"))
      (node (ref "R77") (pin "1") (pinfunction "1_1") (pintype "passive"))
      (node (ref "U$18") (pin "1") (pinfunction "P$1_1") (pintype "bidirectional"))
      (node (ref "U$18") (pin "2") (pinfunction "P$1_2") (pintype "bidirectional"))
      (node (ref "U$18") (pin "3") (pinfunction "P$1_3") (pintype "bidirectional"))
      (node (ref "U$18") (pin "4") (pinfunction "P$1_4") (pintype "bidirectional"))
      (node (ref "U$18") (pin "P$1") (pinfunction "P$1_P$1") (pintype "bidirectional"))
      (node (ref "U$18") (pin "P$2") (pinfunction "P$1_P$2") (pintype "bidirectional"))
    )
    (net (code "39") (name "/SP-") (class "Default")
      (node (ref "LED_Y") (pin "C") (pinfunction "C_C") (pintype "passive"))
      (node (ref "U$2") (pin "1") (pinfunction "P$1_1") (pintype "bidirectional"))
      (node (ref "U$2") (pin "2") (pinfunction "P$1_2") (pintype "bidirectional"))
      (node (ref "U$2") (pin "3") (pinfunction "P$1_3") (pintype "bidirectional"))
      (node (ref "U$2") (pin "4") (pinfunction "P$1_4") (pintype "bidirectional"))
      (node (ref "U$2") (pin "P$1") (pinfunction "P$1_P$1") (pintype "bidirectional"))
      (node (ref "U$2") (pin "P$2") (pinfunction "P$1_P$2") (pintype "bidirectional"))
    )
    (net (code "40") (name "/SP-1") (class "Default")
      (node (ref "FS8205") (pin "67") (pinfunction "S2_67") (pintype "bidirectional"))
      (node (ref "U$22") (pin "7") (pinfunction "EM1_7") (pintype "bidirectional"))
      (node (ref "U$4") (pin "1") (pinfunction "P$1_1") (pintype "bidirectional"))
      (node (ref "U$4") (pin "2") (pinfunction "P$1_2") (pintype "bidirectional"))
      (node (ref "U$4") (pin "3") (pinfunction "P$1_3") (pintype "bidirectional"))
      (node (ref "U$4") (pin "4") (pinfunction "P$1_4") (pintype "bidirectional"))
      (node (ref "U$4") (pin "P$1") (pinfunction "P$1_P$1") (pintype "bidirectional"))
      (node (ref "U$4") (pin "P$2") (pinfunction "P$1_P$2") (pintype "bidirectional"))
    )
    (net (code "41") (name "/SP-2") (class "Default")
      (node (ref "U$19") (pin "1") (pinfunction "P$1_1") (pintype "bidirectional"))
      (node (ref "U$19") (pin "2") (pinfunction "P$1_2") (pintype "bidirectional"))
      (node (ref "U$19") (pin "3") (pinfunction "P$1_3") (pintype "bidirectional"))
      (node (ref "U$19") (pin "4") (pinfunction "P$1_4") (pintype "bidirectional"))
      (node (ref "U$19") (pin "P$1") (pinfunction "P$1_P$1") (pintype "bidirectional"))
      (node (ref "U$19") (pin "P$2") (pinfunction "P$1_P$2") (pintype "bidirectional"))
    )
    (net (code "42") (name "/SP-3") (class "Default")
      (node (ref "U$21") (pin "1") (pinfunction "P$1_1") (pintype "bidirectional"))
      (node (ref "U$21") (pin "2") (pinfunction "P$1_2") (pintype "bidirectional"))
      (node (ref "U$21") (pin "3") (pinfunction "P$1_3") (pintype "bidirectional"))
      (node (ref "U$21") (pin "4") (pinfunction "P$1_4") (pintype "bidirectional"))
      (node (ref "U$21") (pin "P$1") (pinfunction "P$1_P$1") (pintype "bidirectional"))
      (node (ref "U$21") (pin "P$2") (pinfunction "P$1_P$2") (pintype "bidirectional"))
    )
    (net (code "43") (name "/TIME") (class "Default")
      (node (ref "BKU") (pin "14") (pinfunction "14_14") (pintype "passive"))
      (node (ref "JP1") (pin "15") (pinfunction "15_15") (pintype "passive"))
      (node (ref "JP2") (pin "15") (pinfunction "15_15") (pintype "passive"))
      (node (ref "JP3") (pin "15") (pinfunction "15_15") (pintype "passive"))
      (node (ref "JP4") (pin "15") (pinfunction "15_15") (pintype "passive"))
      (node (ref "JP5") (pin "15") (pinfunction "15_15") (pintype "passive"))
      (node (ref "JP6") (pin "15") (pinfunction "15_15") (pintype "passive"))
    )
    (net (code "44") (name "/TIME-ES") (class "Default")
      (node (ref "BKU") (pin "13") (pinfunction "13_13") (pintype "passive"))
      (node (ref "BSK5") (pin "8") (pinfunction "8_8") (pintype "passive"))
    )
    (net (code "45") (name "Net-(FS8205-G1)") (class "Default")
      (node (ref "FS8205") (pin "4") (pinfunction "G1_4") (pintype "bidirectional"))
      (node (ref "R3") (pin "1") (pinfunction "1_1") (pintype "passive"))
      (node (ref "R7") (pin "1") (pinfunction "1_1") (pintype "passive"))
    )
    (net (code "46") (name "Net-(FS8205-G2)") (class "Default")
      (node (ref "FS8205") (pin "5") (pinfunction "G2_5") (pintype "bidirectional"))
      (node (ref "R4") (pin "2") (pinfunction "2_2") (pintype "passive"))
      (node (ref "R5") (pin "1") (pinfunction "1_1") (pintype "passive"))
    )
    (net (code "47") (name "Net-(INA-IN+)") (class "Default")
      (node (ref "C41") (pin "1") (pinfunction "1_1") (pintype "passive"))
      (node (ref "INA") (pin "1") (pinfunction "IN+_1") (pintype "bidirectional"))
      (node (ref "R76") (pin "2") (pinfunction "2_2") (pintype "passive"))
    )
    (net (code "48") (name "Net-(INA-IN-)") (class "Default")
      (node (ref "C41") (pin "2") (pinfunction "2_2") (pintype "passive"))
      (node (ref "INA") (pin "2") (pinfunction "IN-_2") (pintype "bidirectional"))
      (node (ref "R77") (pin "2") (pinfunction "2_2") (pintype "passive"))
    )
    (net (code "49") (name "Net-(LED-B-PadC)") (class "Default")
      (node (ref "LED-B") (pin "C") (pinfunction "C_C") (pintype "passive"))
      (node (ref "R11") (pin "1") (pinfunction "1_1") (pintype "passive"))
    )
    (net (code "50") (name "Net-(LED-G1-PadA)") (class "Default")
      (node (ref "LED-G1") (pin "A") (pinfunction "A_A") (pintype "passive"))
      (node (ref "R16") (pin "2") (pinfunction "2_2") (pintype "passive"))
    )
    (net (code "51") (name "Net-(LED-G2-PadA)") (class "Default")
      (node (ref "LED-G2") (pin "A") (pinfunction "A_A") (pintype "passive"))
      (node (ref "R15") (pin "2") (pinfunction "2_2") (pintype "passive"))
    )
    (net (code "52") (name "Net-(LED-G3-PadA)") (class "Default")
      (node (ref "LED-G3") (pin "A") (pinfunction "A_A") (pintype "passive"))
      (node (ref "R17") (pin "2") (pinfunction "2_2") (pintype "passive"))
    )
    (net (code "53") (name "Net-(LED-G4-PadA)") (class "Default")
      (node (ref "LED-G4") (pin "A") (pinfunction "A_A") (pintype "passive"))
      (node (ref "R21") (pin "2") (pinfunction "2_2") (pintype "passive"))
    )
    (net (code "54") (name "Net-(LED-G5-PadA)") (class "Default")
      (node (ref "LED-G5") (pin "A") (pinfunction "A_A") (pintype "passive"))
      (node (ref "R22") (pin "2") (pinfunction "2_2") (pintype "passive"))
    )
    (net (code "55") (name "Net-(LED-G6-PadA)") (class "Default")
      (node (ref "LED-G6") (pin "A") (pinfunction "A_A") (pintype "passive"))
      (node (ref "R23") (pin "2") (pinfunction "2_2") (pintype "passive"))
    )
    (net (code "56") (name "Net-(LED-R-PadC)") (class "Default")
      (node (ref "LED-R") (pin "C") (pinfunction "C_C") (pintype "passive"))
      (node (ref "R19") (pin "1") (pinfunction "1_1") (pintype "passive"))
    )
    (net (code "57") (name "Net-(LED_Y-PadA)") (class "Default")
      (node (ref "LED_Y") (pin "A") (pinfunction "A_A") (pintype "passive"))
      (node (ref "R10") (pin "2") (pinfunction "2_2") (pintype "passive"))
    )
    (net (code "58") (name "Net-(SI2302-1-D)") (class "Default")
      (node (ref "R11") (pin "2") (pinfunction "2_2") (pintype "passive"))
      (node (ref "SI2302-1") (pin "3") (pinfunction "D_3") (pintype "bidirectional"))
      (node (ref "U$24") (pin "2") (pinfunction "GND_2") (pintype "bidirectional"))
    )
    (net (code "59") (name "Net-(SI2302-1-G)") (class "Default")
      (node (ref "R18") (pin "1") (pinfunction "1_1") (pintype "passive"))
      (node (ref "R32") (pin "1") (pinfunction "1_1") (pintype "passive"))
      (node (ref "SI2302-1") (pin "1") (pinfunction "G_1") (pintype "bidirectional"))
    )
    (net (code "60") (name "Net-(SI2302-2-D)") (class "Default")
      (node (ref "R19") (pin "2") (pinfunction "2_2") (pintype "passive"))
      (node (ref "SI2302-2") (pin "3") (pinfunction "D_3") (pintype "bidirectional"))
      (node (ref "U$27") (pin "P$1") (pinfunction "P$1_P$1") (pintype "bidirectional"))
      (node (ref "U$27") (pin "P$4") (pinfunction "P$1_P$4") (pintype "bidirectional"))
      (node (ref "U$28") (pin "P$1") (pinfunction "P$1_P$1") (pintype "bidirectional"))
      (node (ref "U$28") (pin "P$4") (pinfunction "P$1_P$4") (pintype "bidirectional"))
      (node (ref "U$29") (pin "P$1") (pinfunction "P$1_P$1") (pintype "bidirectional"))
      (node (ref "U$29") (pin "P$4") (pinfunction "P$1_P$4") (pintype "bidirectional"))
      (node (ref "U$30") (pin "P$1") (pinfunction "P$1_P$1") (pintype "bidirectional"))
      (node (ref "U$30") (pin "P$4") (pinfunction "P$1_P$4") (pintype "bidirectional"))
    )
    (net (code "61") (name "Net-(SI2302-2-G)") (class "Default")
      (node (ref "R20") (pin "1") (pinfunction "1_1") (pintype "passive"))
      (node (ref "R33") (pin "1") (pinfunction "1_1") (pintype "passive"))
      (node (ref "SI2302-2") (pin "1") (pinfunction "G_1") (pintype "bidirectional"))
    )
    (net (code "62") (name "Net-(SI2302-3-G)") (class "Default")
      (node (ref "R14") (pin "2") (pinfunction "2_2") (pintype "passive"))
      (node (ref "R31") (pin "1") (pinfunction "1_1") (pintype "passive"))
      (node (ref "SI2302-3") (pin "1") (pinfunction "G_1") (pintype "bidirectional"))
    )
    (net (code "63") (name "Net-(SI2302-4-G)") (class "Default")
      (node (ref "R13") (pin "1") (pinfunction "1_1") (pintype "passive"))
      (node (ref "R26") (pin "1") (pinfunction "1_1") (pintype "passive"))
      (node (ref "SI2302-4") (pin "1") (pinfunction "G_1") (pintype "bidirectional"))
    )
    (net (code "64") (name "Net-(SI2302-5-G)") (class "Default")
      (node (ref "R12") (pin "2") (pinfunction "2_2") (pintype "passive"))
      (node (ref "R30") (pin "1") (pinfunction "1_1") (pintype "passive"))
      (node (ref "SI2302-5") (pin "1") (pinfunction "G_1") (pintype "bidirectional"))
    )
    (net (code "65") (name "Net-(SI2302-6-G)") (class "Default")
      (node (ref "R27") (pin "1") (pinfunction "1_1") (pintype "passive"))
      (node (ref "R9") (pin "2") (pinfunction "2_2") (pintype "passive"))
      (node (ref "SI2302-6") (pin "1") (pinfunction "G_1") (pintype "bidirectional"))
    )
    (net (code "66") (name "Net-(SI2302-7-G)") (class "Default")
      (node (ref "R29") (pin "1") (pinfunction "1_1") (pintype "passive"))
      (node (ref "R8") (pin "1") (pinfunction "1_1") (pintype "passive"))
      (node (ref "SI2302-7") (pin "1") (pinfunction "G_1") (pintype "bidirectional"))
    )
    (net (code "67") (name "Net-(SI2302-8-G)") (class "Default")
      (node (ref "R28") (pin "1") (pinfunction "1_1") (pintype "passive"))
      (node (ref "R6") (pin "2") (pinfunction "2_2") (pintype "passive"))
      (node (ref "SI2302-8") (pin "1") (pinfunction "G_1") (pintype "bidirectional"))
    )
    (net (code "68") (name "Net-(U$22-AN1)") (class "Default")
      (node (ref "R1") (pin "2") (pinfunction "2_2") (pintype "passive"))
      (node (ref "R24") (pin "1") (pinfunction "1_1") (pintype "passive"))
      (node (ref "U$22") (pin "1") (pinfunction "AN1_1") (pintype "bidirectional"))
    )
    (net (code "69") (name "Net-(U$22-AN2)") (class "Default")
      (node (ref "R2") (pin "2") (pinfunction "2_2") (pintype "passive"))
      (node (ref "R25") (pin "1") (pinfunction "1_1") (pintype "passive"))
      (node (ref "U$22") (pin "3") (pinfunction "AN2_3") (pintype "bidirectional"))
    )
    (net (code "70") (name "Net-(U$22-COL1)") (class "Default")
      (node (ref "R5") (pin "2") (pinfunction "2_2") (pintype "passive"))
      (node (ref "U$22") (pin "8") (pinfunction "COL1_8") (pintype "bidirectional"))
    )
    (net (code "71") (name "Net-(U$22-COL2)") (class "Default")
      (node (ref "R3") (pin "2") (pinfunction "2_2") (pintype "passive"))
      (node (ref "U$22") (pin "6") (pinfunction "COL2_6") (pintype "bidirectional"))
    )
  )
)
